# STM32-DHT11-LCD-Schematic.net
KiCad netlist of a schematic drawn in Altium Designer
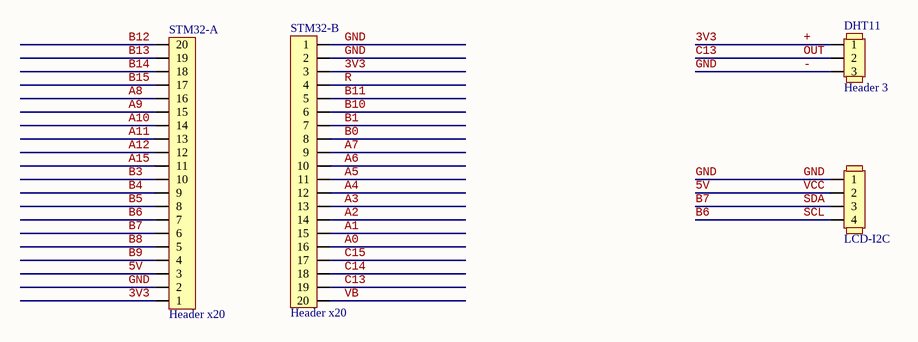
[diagram p0: STM32-DHT11-LCD-Schematic.SchDoc]

(export (version "E")
  (design (tool "Eeschema 10.0.6"))
  (components
    (comp (ref "DHT11") (value "Header 3") (footprint "HEADER x3") (libsource (lib "Duc") (part "Header 3")))
    (comp (ref "LCD-I2C")
      (value "Header 4")
      (footprint "HEADER x4")
      (libsource (lib "Duc") (part "Header 4"))
    )
    (comp (ref "STM32-A")
      (value "Header x20")
      (footprint "HEADER X20")
      (libsource (lib "") (part "Header x20_1"))
    )
    (comp (ref "STM32-B")
      (value "Header x20")
      (footprint "HEADER X20")
      (libsource (lib "Duc") (part "Header x20"))
    )
  )
  (nets
    (net (code "1") (name "/+") (class "Default")
      (node (ref "DHT11") (pin "1") (pinfunction "1_1") (pintype "passive"))
      (node (ref "STM32-A") (pin "1") (pinfunction "1_1") (pintype "passive"))
      (node (ref "STM32-B") (pin "3") (pinfunction "3_3") (pintype "passive"))
    )
    (net (code "2") (name "/-") (class "Default")
      (node (ref "DHT11") (pin "3") (pinfunction "3_3") (pintype "passive"))
      (node (ref "LCD-I2C") (pin "1") (pinfunction "1_1") (pintype "passive"))
      (node (ref "STM32-A") (pin "2") (pinfunction "2_2") (pintype "passive"))
      (node (ref "STM32-B") (pin "1") (pinfunction "1_1") (pintype "passive"))
      (node (ref "STM32-B") (pin "2") (pinfunction "2_2") (pintype "passive"))
    )
    (net (code "3") (name "/5V") (class "Default")
      (node (ref "LCD-I2C") (pin "2") (pinfunction "2_2") (pintype "passive"))
      (node (ref "STM32-A") (pin "3") (pinfunction "3_3") (pintype "passive"))
    )
    (net (code "4") (name "/A0") (class "Default")
      (node (ref "STM32-B") (pin "16") (pinfunction "16_16") (pintype "passive"))
    )
    (net (code "5") (name "/A1") (class "Default")
      (node (ref "STM32-B") (pin "15") (pinfunction "15_15") (pintype "passive"))
    )
    (net (code "6") (name "/A2") (class "Default")
      (node (ref "STM32-B") (pin "14") (pinfunction "14_14") (pintype "passive"))
    )
    (net (code "7") (name "/A3") (class "Default")
      (node (ref "STM32-B") (pin "13") (pinfunction "13_13") (pintype "passive"))
    )
    (net (code "8") (name "/A4") (class "Default")
      (node (ref "STM32-B") (pin "12") (pinfunction "12_12") (pintype "passive"))
    )
    (net (code "9") (name "/A5") (class "Default")
      (node (ref "STM32-B") (pin "11") (pinfunction "11_11") (pintype "passive"))
    )
    (net (code "10") (name "/A6") (class "Default")
      (node (ref "STM32-B") (pin "10") (pinfunction "10_10") (pintype "passive"))
    )
    (net (code "11") (name "/A7") (class "Default")
      (node (ref "STM32-B") (pin "9") (pinfunction "9_9") (pintype "passive"))
    )
    (net (code "12") (name "/A8") (class "Default")
      (node (ref "STM32-A") (pin "16") (pinfunction "16_16") (pintype "passive"))
    )
    (net (code "13") (name "/A9") (class "Default")
      (node (ref "STM32-A") (pin "15") (pinfunction "15_15") (pintype "passive"))
    )
    (net (code "14") (name "/A10") (class "Default")
      (node (ref "STM32-A") (pin "14") (pinfunction "14_14") (pintype "passive"))
    )
    (net (code "15") (name "/A11") (class "Default")
      (node (ref "STM32-A") (pin "13") (pinfunction "13_13") (pintype "passive"))
    )
    (net (code "16") (name "/A12") (class "Default")
      (node (ref "STM32-A") (pin "12") (pinfunction "12_12") (pintype "passive"))
    )
    (net (code "17") (name "/A15") (class "Default")
      (node (ref "STM32-A") (pin "11") (pinfunction "11_11") (pintype "passive"))
    )
    (net (code "18") (name "/B0") (class "Default")
      (node (ref "STM32-B") (pin "8") (pinfunction "8_8") (pintype "passive"))
    )
    (net (code "19") (name "/B1") (class "Default")
      (node (ref "STM32-B") (pin "7") (pinfunction "7_7") (pintype "passive"))
    )
    (net (code "20") (name "/B3") (class "Default")
      (node (ref "STM32-A") (pin "10") (pinfunction "10_10") (pintype "passive"))
    )
    (net (code "21") (name "/B4") (class "Default")
      (node (ref "STM32-A") (pin "9") (pinfunction "9_9") (pintype "passive"))
    )
    (net (code "22") (name "/B5") (class "Default")
      (node (ref "STM32-A") (pin "8") (pinfunction "8_8") (pintype "passive"))
    )
    (net (code "23") (name "/B6") (class "Default")
      (node (ref "LCD-I2C") (pin "4") (pinfunction "4_4") (pintype "passive"))
      (node (ref "STM32-A") (pin "7") (pinfunction "7_7") (pintype "passive"))
    )
    (net (code "24") (name "/B7") (class "Default")
      (node (ref "LCD-I2C") (pin "3") (pinfunction "3_3") (pintype "passive"))
      (node (ref "STM32-A") (pin "6") (pinfunction "6_6") (pintype "passive"))
    )
    (net (code "25") (name "/B8") (class "Default")
      (node (ref "STM32-A") (pin "5") (pinfunction "5_5") (pintype "passive"))
    )
    (net (code "26") (name "/B9") (class "Default")
      (node (ref "STM32-A") (pin "4") (pinfunction "4_4") (pintype "passive"))
    )
    (net (code "27") (name "/B10") (class "Default")
      (node (ref "STM32-B") (pin "6") (pinfunction "6_6") (pintype "passive"))
    )
    (net (code "28") (name "/B11") (class "Default")
      (node (ref "STM32-B") (pin "5") (pinfunction "5_5") (pintype "passive"))
    )
    (net (code "29") (name "/B12") (class "Default")
      (node (ref "STM32-A") (pin "20") (pinfunction "20_20") (pintype "passive"))
    )
    (net (code "30") (name "/B13") (class "Default")
      (node (ref "STM32-A") (pin "19") (pinfunction "19_19") (pintype "passive"))
    )
    (net (code "31") (name "/B14") (class "Default")
      (node (ref "STM32-A") (pin "18") (pinfunction "18_18") (pintype "passive"))
    )
    (net (code "32") (name "/B15") (class "Default")
      (node (ref "STM32-A") (pin "17") (pinfunction "17_17") (pintype "passive"))
    )
    (net (code "33") (name "/C13") (class "Default")
      (node (ref "DHT11") (pin "2") (pinfunction "2_2") (pintype "passive"))
      (node (ref "STM32-B") (pin "19") (pinfunction "19_19") (pintype "passive"))
    )
    (net (code "34") (name "/C14") (class "Default")
      (node (ref "STM32-B") (pin "18") (pinfunction "18_18") (pintype "passive"))
    )
    (net (code "35") (name "/C15") (class "Default")
      (node (ref "STM32-B") (pin "17") (pinfunction "17_17") (pintype "passive"))
    )
    (net (code "36") (name "/R") (class "Default")
      (node (ref "STM32-B") (pin "4") (pinfunction "4_4") (pintype "passive"))
    )
    (net (code "37") (name "/VB") (class "Default")
      (node (ref "STM32-B") (pin "20") (pinfunction "20_20") (pintype "passive"))
    )
  )
)
